# GPS.net
KiCad netlist of a schematic drawn in Altium Designer
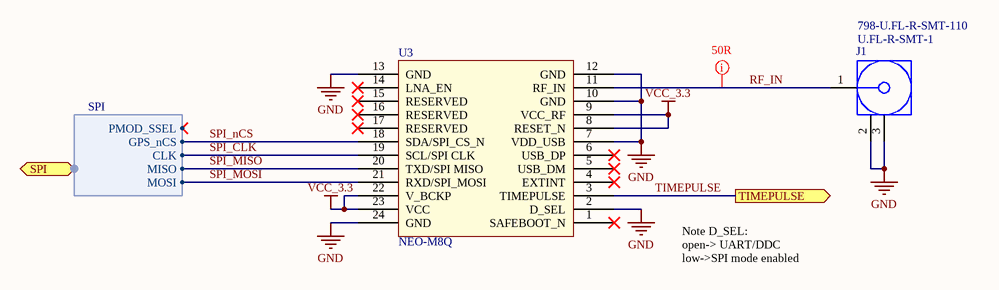
[diagram p0: GPS.SchDoc]

(export (version "E")
  (design (tool "Eeschema 10.0.6"))
  (components
    (comp (ref "J1")
      (value "U.FL-R-SMT-1")
      (footprint "U.FL-R-SMT-1")
      (description "Hirose U.FL SMT connector")
      (fields (field (name "SUPPLIER PART NUMBER 1") "798-U.FL-R-SMT-110"))
      (libsource (lib "HEPIA Vault") (part "CMP-001-0013-A.3"))
    )
    (comp (ref "U3")
      (value "NEO-M8Q")
      (footprint "NEO")
      (description "u-blox M8 concurrent GNSS LCC module, TCXO, ROM, SAW, LNA")
      (libsource (lib "HEPIA Vault") (part "NEO"))
    )
  )
  (nets
    (net (code "2") (name "/RF_IN") (class "Default")
      (node (ref "J1") (pin "1") (pinfunction "Signal_1") (pintype "passive"))
      (node (ref "U3") (pin "11") (pinfunction "RF_IN_11") (pintype "passive"))
    )
    (net (code "3") (name "/SPI_CLK") (class "Default")
      (node (ref "U3") (pin "19") (pinfunction "SCL/SPI_CLK_19") (pintype "passive"))
    )
    (net (code "4") (name "/SPI_MISO") (class "Default")
      (node (ref "U3") (pin "20") (pinfunction "TXD/SPI_MISO_20") (pintype "passive"))
    )
    (net (code "5") (name "/SPI_MOSI") (class "Default")
      (node (ref "U3") (pin "21") (pinfunction "RXD/SPI_MOSI_21") (pintype "passive"))
    )
    (net (code "6") (name "/SPI_nCS") (class "Default")
      (node (ref "U3") (pin "18") (pinfunction "SDA/SPI_CS_N_18") (pintype "passive"))
    )
    (net (code "7") (name "/TIMEPULSE") (class "Default")
      (node (ref "U3") (pin "3") (pinfunction "TIMEPULSE_3") (pintype "passive"))
    )
    (net (code "9") (name "GND") (class "Default")
      (node (ref "J1") (pin "2") (pinfunction "GND_2") (pintype "power_in"))
      (node (ref "J1") (pin "3") (pinfunction "GND_3") (pintype "power_in"))
      (node (ref "U3") (pin "10") (pinfunction "GND_10") (pintype "passive"))
      (node (ref "U3") (pin "12") (pinfunction "GND_12") (pintype "passive"))
      (node (ref "U3") (pin "13") (pinfunction "GND_13") (pintype "passive"))
      (node (ref "U3") (pin "2") (pinfunction "D_SEL_2") (pintype "passive"))
      (node (ref "U3") (pin "24") (pinfunction "GND_24") (pintype "passive"))
      (node (ref "U3") (pin "7") (pinfunction "VDD_USB_7") (pintype "passive"))
    )
    (net (code "10") (name "VCC_3.3") (class "Default")
      (node (ref "U3") (pin "22") (pinfunction "V_BCKP_22") (pintype "passive"))
      (node (ref "U3") (pin "23") (pinfunction "VCC_23") (pintype "passive"))
      (node (ref "U3") (pin "8") (pinfunction "RESET_N_8") (pintype "passive"))
      (node (ref "U3") (pin "9") (pinfunction "VCC_RF_9") (pintype "passive"))
    )
    (net (code "11") (name "unconnected-(U3-EXTINT-Pad4)") (class "Default")
      (node (ref "U3") (pin "4") (pinfunction "EXTINT_4") (pintype "passive+no_connect"))
    )
    (net (code "12") (name "unconnected-(U3-LNA_EN-Pad14)") (class "Default")
      (node (ref "U3") (pin "14") (pinfunction "LNA_EN_14") (pintype "passive+no_connect"))
    )
    (net (code "13") (name "unconnected-(U3-RESERVED-Pad15)") (class "Default")
      (node (ref "U3") (pin "15") (pinfunction "RESERVED_15") (pintype "passive+no_connect"))
    )
    (net (code "14") (name "unconnected-(U3-RESERVED-Pad16)") (class "Default")
      (node (ref "U3") (pin "16") (pinfunction "RESERVED_16") (pintype "passive+no_connect"))
    )
    (net (code "15") (name "unconnected-(U3-RESERVED-Pad17)") (class "Default")
      (node (ref "U3") (pin "17") (pinfunction "RESERVED_17") (pintype "passive+no_connect"))
    )
    (net (code "16") (name "unconnected-(U3-SAFEBOOT_N-Pad1)") (class "Default")
      (node (ref "U3") (pin "1") (pinfunction "SAFEBOOT_N_1") (pintype "passive+no_connect"))
    )
    (net (code "17") (name "unconnected-(U3-USB_DM-Pad5)") (class "Default")
      (node (ref "U3") (pin "5") (pinfunction "USB_DM_5") (pintype "passive+no_connect"))
    )
    (net (code "18") (name "unconnected-(U3-USB_DP-Pad6)") (class "Default")
      (node (ref "U3") (pin "6") (pinfunction "USB_DP_6") (pintype "passive+no_connect"))
    )
  )
)
